# musicbox.net
KiCad netlist of a schematic drawn in EAGLE
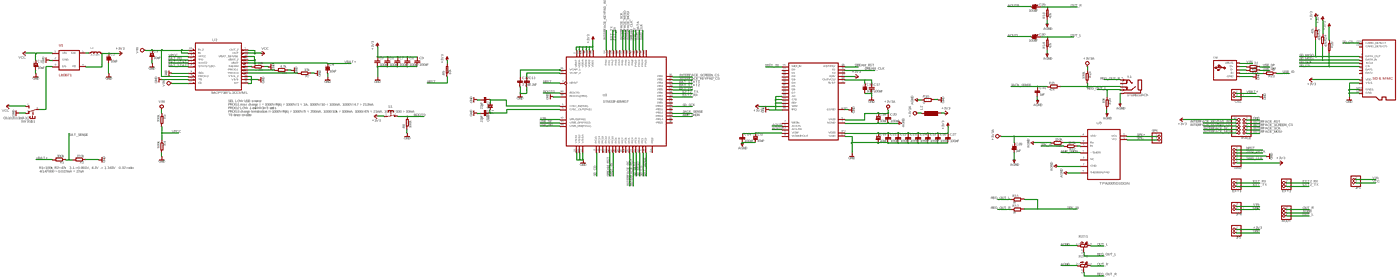
[diagram p0: schematic, sheet 1, overview]
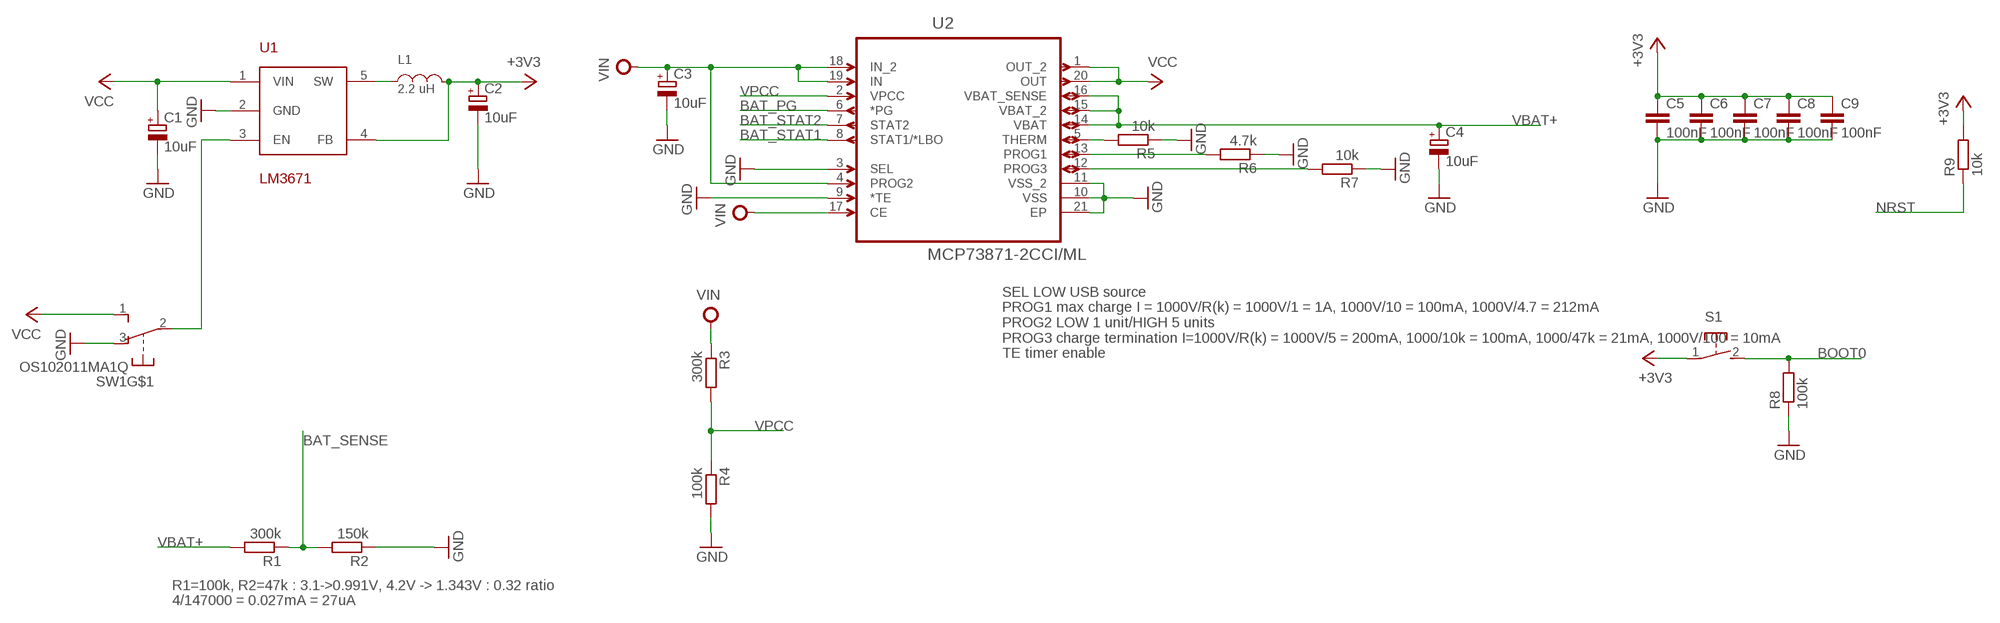
[diagram p1: schematic, sheet 1, part 1 of 4]
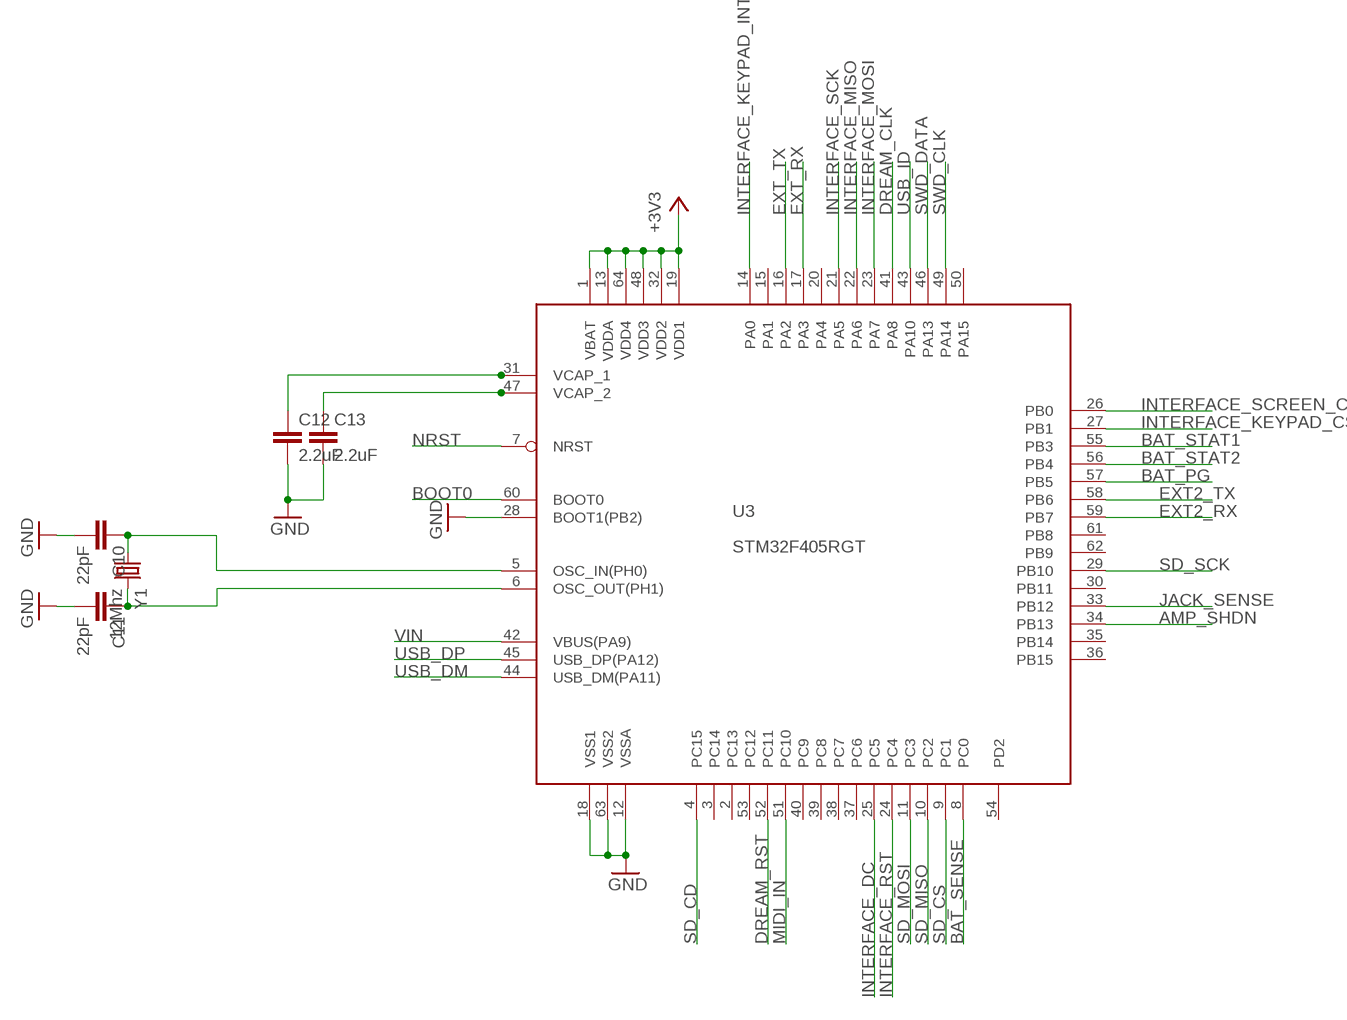
[diagram p2: schematic, sheet 1, part 2 of 4]
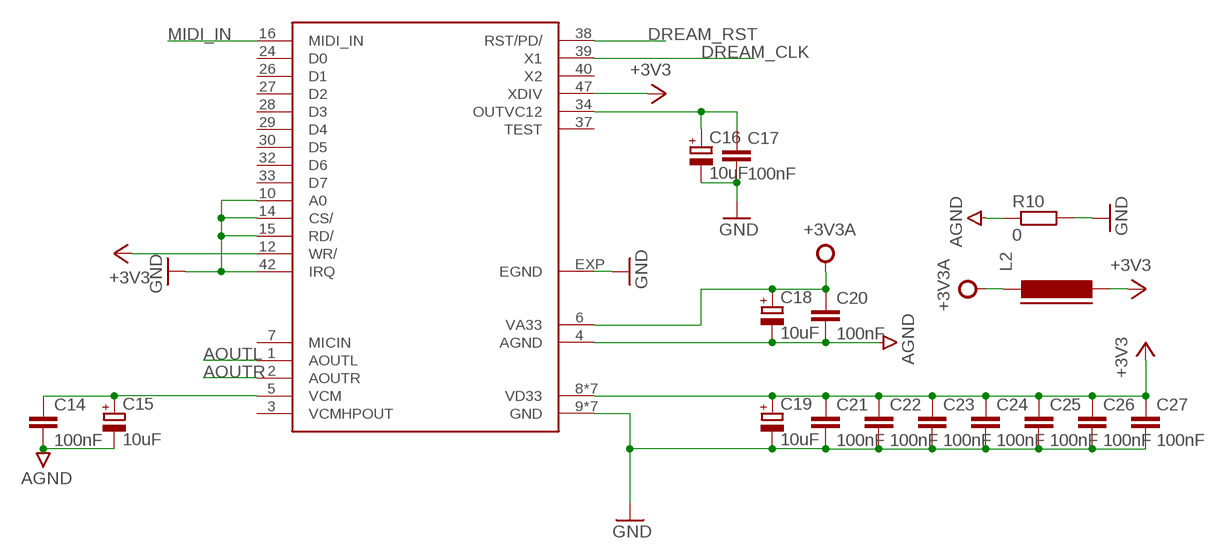
[diagram p3: schematic, sheet 1, part 3 of 4]
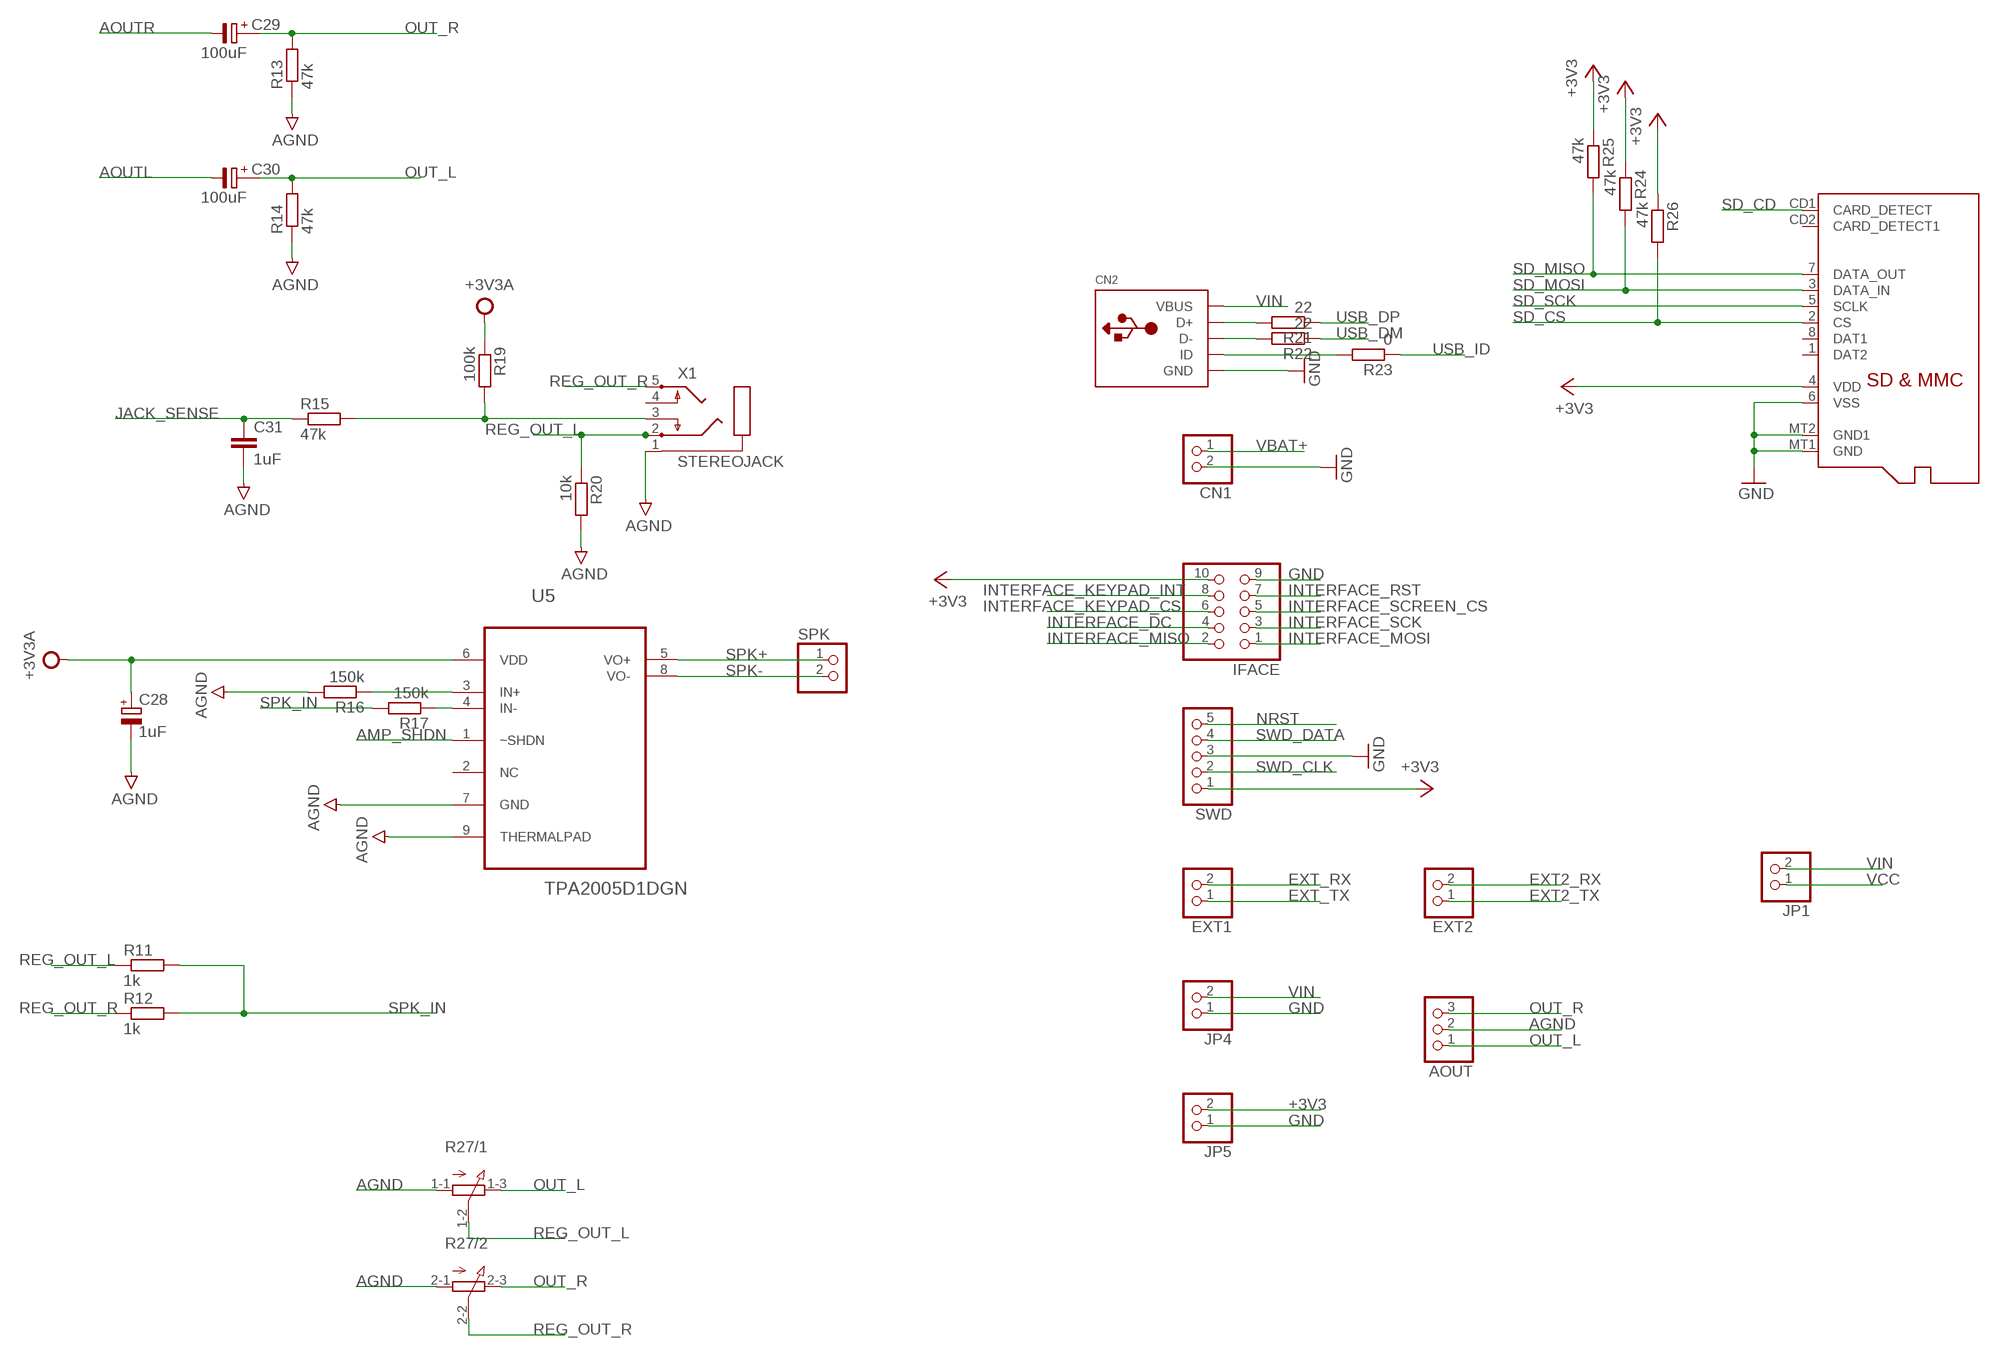
[diagram p4: schematic, sheet 1, part 4 of 4]

(export (version "E")
  (design (tool "Eeschema 10.0.6"))
  (components
    (comp (ref "AOUT")
      (value "HEADER-1X3ROUND")
      (footprint "eagle-import:1X03_ROUND")
      (libsource (lib "eagle-import") (part "HEADER-1X3ROUND"))
    )
    (comp (ref "C1")
      (value "10uF")
      (footprint "eagle-import:A_3216-18R")
      (libsource (lib "eagle-import") (part "CPOL-EUA/3216-18R"))
    )
    (comp (ref "C2")
      (value "10uF")
      (footprint "eagle-import:A_3216-18R")
      (libsource (lib "eagle-import") (part "CPOL-EUA/3216-18R"))
    )
    (comp (ref "C3")
      (value "10uF")
      (footprint "eagle-import:A_3216-18R")
      (libsource (lib "eagle-import") (part "CPOL-EUA/3216-18R"))
    )
    (comp (ref "C4")
      (value "10uF")
      (footprint "eagle-import:A_3216-18R")
      (libsource (lib "eagle-import") (part "CPOL-EUA/3216-18R"))
    )
    (comp (ref "C5")
      (value "100nF")
      (footprint "eagle-import:C0603K")
      (libsource (lib "eagle-import") (part "C-EUC0603K"))
    )
    (comp (ref "C6")
      (value "100nF")
      (footprint "eagle-import:C0603K")
      (libsource (lib "eagle-import") (part "C-EUC0603K"))
    )
    (comp (ref "C7")
      (value "100nF")
      (footprint "eagle-import:C0603K")
      (libsource (lib "eagle-import") (part "C-EUC0603K"))
    )
    (comp (ref "C8")
      (value "100nF")
      (footprint "eagle-import:C0603K")
      (libsource (lib "eagle-import") (part "C-EUC0603K"))
    )
    (comp (ref "C9")
      (value "100nF")
      (footprint "eagle-import:C0603K")
      (libsource (lib "eagle-import") (part "C-EUC0603K"))
    )
    (comp (ref "C10")
      (value "22pF")
      (footprint "eagle-import:C0603K")
      (libsource (lib "eagle-import") (part "C-EUC0603K"))
    )
    (comp (ref "C11")
      (value "22pF")
      (footprint "eagle-import:C0603K")
      (libsource (lib "eagle-import") (part "C-EUC0603K"))
    )
    (comp (ref "C12")
      (value "2.2uF")
      (footprint "eagle-import:C0603K")
      (libsource (lib "eagle-import") (part "C-EUC0603K"))
    )
    (comp (ref "C13")
      (value "2.2uF")
      (footprint "eagle-import:C0603K")
      (libsource (lib "eagle-import") (part "C-EUC0603K"))
    )
    (comp (ref "C14")
      (value "100nF")
      (footprint "eagle-import:C0603K")
      (libsource (lib "eagle-import") (part "C-EUC0603K"))
    )
    (comp (ref "C15")
      (value "10uF")
      (footprint "eagle-import:A_3216-18R")
      (libsource (lib "eagle-import") (part "CPOL-EUA/3216-18R"))
    )
    (comp (ref "C16")
      (value "10uF")
      (footprint "eagle-import:A_3216-18R")
      (libsource (lib "eagle-import") (part "CPOL-EUA/3216-18R"))
    )
    (comp (ref "C17")
      (value "100nF")
      (footprint "eagle-import:C0603K")
      (libsource (lib "eagle-import") (part "C-EUC0603K"))
    )
    (comp (ref "C18")
      (value "10uF")
      (footprint "eagle-import:A_3216-18R")
      (libsource (lib "eagle-import") (part "CPOL-EUA/3216-18R"))
    )
    (comp (ref "C19")
      (value "10uF")
      (footprint "eagle-import:A_3216-18R")
      (libsource (lib "eagle-import") (part "CPOL-EUA/3216-18R"))
    )
    (comp (ref "C20")
      (value "100nF")
      (footprint "eagle-import:C0603K")
      (libsource (lib "eagle-import") (part "C-EUC0603K"))
    )
    (comp (ref "C21")
      (value "100nF")
      (footprint "eagle-import:C0603K")
      (libsource (lib "eagle-import") (part "C-EUC0603K"))
    )
    (comp (ref "C22")
      (value "100nF")
      (footprint "eagle-import:C0603K")
      (libsource (lib "eagle-import") (part "C-EUC0603K"))
    )
    (comp (ref "C23")
      (value "100nF")
      (footprint "eagle-import:C0603K")
      (libsource (lib "eagle-import") (part "C-EUC0603K"))
    )
    (comp (ref "C24")
      (value "100nF")
      (footprint "eagle-import:C0603K")
      (libsource (lib "eagle-import") (part "C-EUC0603K"))
    )
    (comp (ref "C25")
      (value "100nF")
      (footprint "eagle-import:C0603K")
      (libsource (lib "eagle-import") (part "C-EUC0603K"))
    )
    (comp (ref "C26")
      (value "100nF")
      (footprint "eagle-import:C0603K")
      (libsource (lib "eagle-import") (part "C-EUC0603K"))
    )
    (comp (ref "C27")
      (value "100nF")
      (footprint "eagle-import:C0603K")
      (libsource (lib "eagle-import") (part "C-EUC0603K"))
    )
    (comp (ref "C28")
      (value "1uF")
      (footprint "eagle-import:A_3216-18R")
      (libsource (lib "eagle-import") (part "CPOL-EUA/3216-18R"))
    )
    (comp (ref "C29")
      (value "100uF")
      (footprint "eagle-import:SV-B")
      (libsource (lib "eagle-import") (part "C-PR-SMD-SV-B"))
    )
    (comp (ref "C30")
      (value "100uF")
      (footprint "eagle-import:SV-B")
      (libsource (lib "eagle-import") (part "C-PR-SMD-SV-B"))
    )
    (comp (ref "C31")
      (value "1uF")
      (footprint "eagle-import:C0603K")
      (libsource (lib "eagle-import") (part "C-EUC0603K"))
    )
    (comp (ref "CN1")
      (value "JST_2PIN-THM")
      (footprint "eagle-import:JST-PH-2-THM")
      (libsource (lib "eagle-import") (part "JST_2PIN-THM"))
    )
    (comp (ref "CN2")
      (value "USBMOLEX")
      (footprint "eagle-import:USB-MINIB-THM-MOLEX")
      (libsource (lib "eagle-import") (part "USBMOLEX"))
    )
    (comp (ref "EXT1")
      (value "HEADER-1X2ROUND")
      (footprint "eagle-import:1X02_ROUND")
      (libsource (lib "eagle-import") (part "HEADER-1X2ROUND"))
    )
    (comp (ref "EXT2")
      (value "HEADER-1X2ROUND")
      (footprint "eagle-import:1X02_ROUND")
      (libsource (lib "eagle-import") (part "HEADER-1X2ROUND"))
    )
    (comp (ref "IFACE")
      (value "HEADER-2X5")
      (footprint "eagle-import:2X05")
      (libsource (lib "eagle-import") (part "HEADER-2X5"))
    )
    (comp (ref "JP1")
      (value "HEADER-1X2ROUND")
      (footprint "eagle-import:1X02_ROUND")
      (libsource (lib "eagle-import") (part "HEADER-1X2ROUND"))
    )
    (comp (ref "JP4")
      (value "HEADER-1X2ROUND")
      (footprint "eagle-import:1X02_ROUND")
      (libsource (lib "eagle-import") (part "HEADER-1X2ROUND"))
    )
    (comp (ref "JP5")
      (value "HEADER-1X2ROUND")
      (footprint "eagle-import:1X02_ROUND")
      (libsource (lib "eagle-import") (part "HEADER-1X2ROUND"))
    )
    (comp (ref "L1")
      (value "2.2 uH")
      (footprint "eagle-import:4X4MM")
      (libsource (lib "eagle-import") (part "L4X4MM"))
    )
    (comp (ref "L2")
      (value "FERRITE-0603")
      (footprint "eagle-import:FB603")
      (libsource (lib "eagle-import") (part "FERRITE-0603"))
    )
    (comp (ref "R1")
      (value "300k")
      (footprint "eagle-import:R0603")
      (libsource (lib "eagle-import") (part "R-EU_R0603"))
    )
    (comp (ref "R2")
      (value "150k")
      (footprint "eagle-import:R0603")
      (libsource (lib "eagle-import") (part "R-EU_R0603"))
    )
    (comp (ref "R3")
      (value "300k")
      (footprint "eagle-import:R0603")
      (libsource (lib "eagle-import") (part "R-EU_R0603"))
    )
    (comp (ref "R4")
      (value "100k")
      (footprint "eagle-import:R0603")
      (libsource (lib "eagle-import") (part "R-EU_R0603"))
    )
    (comp (ref "R5")
      (value "10k")
      (footprint "eagle-import:R0603")
      (libsource (lib "eagle-import") (part "R-EU_R0603"))
    )
    (comp (ref "R6")
      (value "4.7k")
      (footprint "eagle-import:R0603")
      (libsource (lib "eagle-import") (part "R-EU_R0603"))
    )
    (comp (ref "R7")
      (value "10k")
      (footprint "eagle-import:R0603")
      (libsource (lib "eagle-import") (part "R-EU_R0603"))
    )
    (comp (ref "R8")
      (value "100k")
      (footprint "eagle-import:R0603")
      (libsource (lib "eagle-import") (part "R-EU_R0603"))
    )
    (comp (ref "R9")
      (value "10k")
      (footprint "eagle-import:R0603")
      (libsource (lib "eagle-import") (part "R-EU_R0603"))
    )
    (comp (ref "R10")
      (value "0")
      (footprint "eagle-import:R0603")
      (libsource (lib "eagle-import") (part "R-EU_R0603"))
    )
    (comp (ref "R11")
      (value "1k")
      (footprint "eagle-import:R0603")
      (libsource (lib "eagle-import") (part "R-EU_R0603"))
    )
    (comp (ref "R12")
      (value "1k")
      (footprint "eagle-import:R0603")
      (libsource (lib "eagle-import") (part "R-EU_R0603"))
    )
    (comp (ref "R13")
      (value "47k")
      (footprint "eagle-import:R0603")
      (libsource (lib "eagle-import") (part "R-EU_R0603"))
    )
    (comp (ref "R14")
      (value "47k")
      (footprint "eagle-import:R0603")
      (libsource (lib "eagle-import") (part "R-EU_R0603"))
    )
    (comp (ref "R15")
      (value "47k")
      (footprint "eagle-import:R0603")
      (libsource (lib "eagle-import") (part "R-EU_R0603"))
    )
    (comp (ref "R16")
      (value "150k")
      (footprint "eagle-import:R0603")
      (libsource (lib "eagle-import") (part "R-EU_R0603"))
    )
    (comp (ref "R17")
      (value "150k")
      (footprint "eagle-import:R0603")
      (libsource (lib "eagle-import") (part "R-EU_R0603"))
    )
    (comp (ref "R19")
      (value "100k")
      (footprint "eagle-import:R0603")
      (libsource (lib "eagle-import") (part "R-EU_R0603"))
    )
    (comp (ref "R20")
      (value "10k")
      (footprint "eagle-import:R0603")
      (libsource (lib "eagle-import") (part "R-EU_R0603"))
    )
    (comp (ref "R21")
      (value "22")
      (footprint "eagle-import:R0603")
      (libsource (lib "eagle-import") (part "R-EU_R0603"))
    )
    (comp (ref "R22")
      (value "22")
      (footprint "eagle-import:R0603")
      (libsource (lib "eagle-import") (part "R-EU_R0603"))
    )
    (comp (ref "R23")
      (value "0")
      (footprint "eagle-import:R0603")
      (libsource (lib "eagle-import") (part "R-EU_R0603"))
    )
    (comp (ref "R24")
      (value "47k")
      (footprint "eagle-import:R0603")
      (libsource (lib "eagle-import") (part "R-EU_R0603"))
    )
    (comp (ref "R25")
      (value "47k")
      (footprint "eagle-import:R0603")
      (libsource (lib "eagle-import") (part "R-EU_R0603"))
    )
    (comp (ref "R26")
      (value "47k")
      (footprint "eagle-import:R0603")
      (libsource (lib "eagle-import") (part "R-EU_R0603"))
    )
    (comp (ref "R27")
      (value "3RP/1610G")
      (footprint "eagle-import:3RP_1610G")
      (libsource (lib "eagle-import") (part "3RP/1610G"))
    )
    (comp (ref "S1")
      (value "31-XX")
      (footprint "eagle-import:B3F-31XX")
      (fields (field (name "MPN") "B3F-3100"))
      (libsource (lib "eagle-import") (part "31-XX"))
    )
    (comp (ref "SPK")
      (value "HEADER-1X2ROUND")
      (footprint "eagle-import:1X02_ROUND")
      (libsource (lib "eagle-import") (part "HEADER-1X2ROUND"))
    )
    (comp (ref "SW1")
      (value "OS102011MA1Q")
      (footprint "eagle-import:OS102011MA1Q")
      (libsource (lib "eagle-import") (part "OS102011MA1Q"))
    )
    (comp (ref "SWD")
      (value "HEADER-1X5ROUND")
      (footprint "eagle-import:1X05_ROUND")
      (libsource (lib "eagle-import") (part "HEADER-1X5ROUND"))
    )
    (comp (ref "U1")
      (value "LM3671")
      (footprint "eagle-import:SOT23-5")
      (libsource (lib "eagle-import") (part "LM3671"))
    )
    (comp (ref "U2")
      (value "MCP73871-2CCI/ML")
      (footprint "eagle-import:QFN50P400X400X100-21N")
      (libsource (lib "eagle-import") (part "MCP73871-2CCI/ML"))
    )
    (comp (ref "U3")
      (value "STM32F405RGT")
      (footprint "eagle-import:LQFP64")
      (libsource (lib "eagle-import") (part "STM32F405RGT"))
    )
    (comp (ref "U4")
      (value "SAM2695")
      (footprint "eagle-import:QFN48")
      (libsource (lib "eagle-import") (part "SAM2695"))
    )
    (comp (ref "U5")
      (value "TPA2005D1DGN")
      (footprint "eagle-import:SOP65P488X107-9N")
      (libsource (lib "eagle-import") (part "TPA2005D1DGN"))
    )
    (comp (ref "U6")
      (value "MICROSD")
      (footprint "eagle-import:MICROSD")
      (libsource (lib "eagle-import") (part "MICROSD"))
    )
    (comp (ref "X1")
      (value "STEREOJACK")
      (footprint "eagle-import:STX3100")
      (libsource (lib "eagle-import") (part "STEREOJACK"))
    )
    (comp (ref "Y1")
      (value "12Mhz")
      (footprint "eagle-import:CRYSTAL-TXC-7A")
      (libsource (lib "eagle-import") (part "CRYSTALTXC-7A"))
    )
  )
  (nets
    (net (code "1") (name "+3V3") (class "Default")
      (node (ref "C19") (pin "+") (pinfunction "+_+") (pintype "passive"))
      (node (ref "C2") (pin "+") (pinfunction "+_+") (pintype "passive"))
      (node (ref "C21") (pin "1") (pinfunction "1_1") (pintype "passive"))
      (node (ref "C22") (pin "1") (pinfunction "1_1") (pintype "passive"))
      (node (ref "C23") (pin "1") (pinfunction "1_1") (pintype "passive"))
      (node (ref "C24") (pin "1") (pinfunction "1_1") (pintype "passive"))
      (node (ref "C25") (pin "1") (pinfunction "1_1") (pintype "passive"))
      (node (ref "C26") (pin "1") (pinfunction "1_1") (pintype "passive"))
      (node (ref "C27") (pin "1") (pinfunction "1_1") (pintype "passive"))
      (node (ref "C5") (pin "1") (pinfunction "1_1") (pintype "passive"))
      (node (ref "C6") (pin "1") (pinfunction "1_1") (pintype "passive"))
      (node (ref "C7") (pin "1") (pinfunction "1_1") (pintype "passive"))
      (node (ref "C8") (pin "1") (pinfunction "1_1") (pintype "passive"))
      (node (ref "C9") (pin "1") (pinfunction "1_1") (pintype "passive"))
      (node (ref "IFACE") (pin "10") (pinfunction "10_10") (pintype "passive"))
      (node (ref "JP5") (pin "2") (pinfunction "2_2") (pintype "passive"))
      (node (ref "L1") (pin "2") (pinfunction "2_2") (pintype "passive"))
      (node (ref "L2") (pin "2") (pinfunction "2_2") (pintype "passive"))
      (node (ref "R24") (pin "1") (pinfunction "1_1") (pintype "passive"))
      (node (ref "R25") (pin "1") (pinfunction "1_1") (pintype "passive"))
      (node (ref "R26") (pin "1") (pinfunction "1_1") (pintype "passive"))
      (node (ref "R9") (pin "2") (pinfunction "2_2") (pintype "passive"))
      (node (ref "S1") (pin "1") (pinfunction "P_1") (pintype "passive"))
      (node (ref "SWD") (pin "1") (pinfunction "1_1") (pintype "passive"))
      (node (ref "U1") (pin "4") (pinfunction "FB_4") (pintype "bidirectional"))
      (node (ref "U3") (pin "1") (pinfunction "VBAT_1") (pintype "power_in"))
      (node (ref "U3") (pin "13") (pinfunction "VDDA_13") (pintype "power_in"))
      (node (ref "U3") (pin "19") (pinfunction "VDD1_19") (pintype "power_in"))
      (node (ref "U3") (pin "32") (pinfunction "VDD2_32") (pintype "power_in"))
      (node (ref "U3") (pin "48") (pinfunction "VDD3_48") (pintype "power_in"))
      (node (ref "U3") (pin "64") (pinfunction "VDD4_64") (pintype "power_in"))
      (node (ref "U4") (pin "11") (pinfunction "VD33_11") (pintype "power_in"))
      (node (ref "U4") (pin "12") (pinfunction "WR/_12") (pintype "input"))
      (node (ref "U4") (pin "20") (pinfunction "VD33_20") (pintype "power_in"))
      (node (ref "U4") (pin "31") (pinfunction "VD33_31") (pintype "power_in"))
      (node (ref "U4") (pin "35") (pinfunction "VD33_35") (pintype "power_in"))
      (node (ref "U4") (pin "41") (pinfunction "VD33_41") (pintype "power_in"))
      (node (ref "U4") (pin "46") (pinfunction "VD33_46") (pintype "power_in"))
      (node (ref "U4") (pin "47") (pinfunction "XDIV_47") (pintype "input"))
      (node (ref "U4") (pin "8") (pinfunction "VD33_8") (pintype "power_in"))
      (node (ref "U6") (pin "4") (pinfunction "VDD_4") (pintype "power_in"))
    )
    (net (code "2") (name "+3V3A") (class "Default")
      (node (ref "C18") (pin "+") (pinfunction "+_+") (pintype "passive"))
      (node (ref "C20") (pin "1") (pinfunction "1_1") (pintype "passive"))
      (node (ref "C28") (pin "+") (pinfunction "+_+") (pintype "passive"))
      (node (ref "L2") (pin "1") (pinfunction "1_1") (pintype "passive"))
      (node (ref "R19") (pin "1") (pinfunction "1_1") (pintype "passive"))
      (node (ref "U4") (pin "6") (pinfunction "VA33_6") (pintype "power_in"))
      (node (ref "U5") (pin "6") (pinfunction "VDD_6") (pintype "power_in"))
    )
    (net (code "3") (name "/AMP_SHDN") (class "Default")
      (node (ref "U3") (pin "34") (pinfunction "PB13_34") (pintype "bidirectional"))
      (node (ref "U5") (pin "1") (pinfunction "~{SHDN}_1") (pintype "passive"))
    )
    (net (code "4") (name "/AOUTL") (class "Default")
      (node (ref "C30") (pin "-") (pinfunction "-_-") (pintype "passive"))
      (node (ref "U4") (pin "1") (pinfunction "AOUTL_1") (pintype "output"))
    )
    (net (code "5") (name "/AOUTR") (class "Default")
      (node (ref "C29") (pin "-") (pinfunction "-_-") (pintype "passive"))
      (node (ref "U4") (pin "2") (pinfunction "AOUTR_2") (pintype "output"))
    )
    (net (code "6") (name "/BAT_PG") (class "Default")
      (node (ref "U2") (pin "6") (pinfunction "*PG_6") (pintype "output"))
      (node (ref "U3") (pin "57") (pinfunction "PB5_57") (pintype "bidirectional"))
    )
    (net (code "7") (name "/BAT_SENSE") (class "Default")
      (node (ref "R1") (pin "1") (pinfunction "1_1") (pintype "passive"))
      (node (ref "R2") (pin "2") (pinfunction "2_2") (pintype "passive"))
      (node (ref "U3") (pin "8") (pinfunction "PC0_8") (pintype "bidirectional"))
    )
    (net (code "8") (name "/BAT_STAT1") (class "Default")
      (node (ref "U2") (pin "8") (pinfunction "STAT1/*LBO_8") (pintype "output"))
      (node (ref "U3") (pin "55") (pinfunction "PB3_55") (pintype "bidirectional"))
    )
    (net (code "9") (name "/BAT_STAT2") (class "Default")
      (node (ref "U2") (pin "7") (pinfunction "STAT2_7") (pintype "output"))
      (node (ref "U3") (pin "56") (pinfunction "PB4_56") (pintype "bidirectional"))
    )
    (net (code "10") (name "/BOOT0") (class "Default")
      (node (ref "R8") (pin "2") (pinfunction "2_2") (pintype "passive"))
      (node (ref "S1") (pin "2") (pinfunction "S_2") (pintype "passive"))
      (node (ref "U3") (pin "60") (pinfunction "BOOT0_60") (pintype "input"))
    )
    (net (code "11") (name "/DREAM_CLK") (class "Default")
      (node (ref "U3") (pin "41") (pinfunction "PA8_41") (pintype "bidirectional"))
      (node (ref "U4") (pin "39") (pinfunction "X1_39") (pintype "bidirectional"))
    )
    (net (code "12") (name "/DREAM_RST") (class "Default")
      (node (ref "U3") (pin "52") (pinfunction "PC11_52") (pintype "bidirectional"))
      (node (ref "U4") (pin "38") (pinfunction "RST/PD/_38") (pintype "input"))
    )
    (net (code "13") (name "/EXT2_RX") (class "Default")
      (node (ref "EXT2") (pin "2") (pinfunction "2_2") (pintype "passive"))
      (node (ref "U3") (pin "59") (pinfunction "PB7_59") (pintype "bidirectional"))
    )
    (net (code "14") (name "/EXT2_TX") (class "Default")
      (node (ref "EXT2") (pin "1") (pinfunction "1_1") (pintype "passive"))
      (node (ref "U3") (pin "58") (pinfunction "PB6_58") (pintype "bidirectional"))
    )
    (net (code "15") (name "/EXT_RX") (class "Default")
      (node (ref "EXT1") (pin "2") (pinfunction "2_2") (pintype "passive"))
      (node (ref "U3") (pin "17") (pinfunction "PA3_17") (pintype "bidirectional"))
    )
    (net (code "16") (name "/EXT_TX") (class "Default")
      (node (ref "EXT1") (pin "1") (pinfunction "1_1") (pintype "passive"))
      (node (ref "U3") (pin "16") (pinfunction "PA2_16") (pintype "bidirectional"))
    )
    (net (code "17") (name "/INTERFACE_DC") (class "Default")
      (node (ref "IFACE") (pin "4") (pinfunction "4_4") (pintype "passive"))
      (node (ref "U3") (pin "25") (pinfunction "PC5_25") (pintype "bidirectional"))
    )
    (net (code "18") (name "/INTERFACE_KEYPAD_CS") (class "Default")
      (node (ref "IFACE") (pin "6") (pinfunction "6_6") (pintype "passive"))
      (node (ref "U3") (pin "27") (pinfunction "PB1_27") (pintype "bidirectional"))
    )
    (net (code "19") (name "/INTERFACE_KEYPAD_INT") (class "Default")
      (node (ref "IFACE") (pin "8") (pinfunction "8_8") (pintype "passive"))
      (node (ref "U3") (pin "14") (pinfunction "PA0_14") (pintype "bidirectional"))
    )
    (net (code "20") (name "/INTERFACE_MISO") (class "Default")
      (node (ref "IFACE") (pin "2") (pinfunction "2_2") (pintype "passive"))
      (node (ref "U3") (pin "22") (pinfunction "PA6_22") (pintype "bidirectional"))
    )
    (net (code "21") (name "/INTERFACE_MOSI") (class "Default")
      (node (ref "IFACE") (pin "1") (pinfunction "1_1") (pintype "passive"))
      (node (ref "U3") (pin "23") (pinfunction "PA7_23") (pintype "bidirectional"))
    )
    (net (code "22") (name "/INTERFACE_RST") (class "Default")
      (node (ref "IFACE") (pin "7") (pinfunction "7_7") (pintype "passive"))
      (node (ref "U3") (pin "24") (pinfunction "PC4_24") (pintype "bidirectional"))
    )
    (net (code "23") (name "/INTERFACE_SCK") (class "Default")
      (node (ref "IFACE") (pin "3") (pinfunction "3_3") (pintype "passive"))
      (node (ref "U3") (pin "21") (pinfunction "PA5_21") (pintype "bidirectional"))
    )
    (net (code "24") (name "/INTERFACE_SCREEN_CS") (class "Default")
      (node (ref "IFACE") (pin "5") (pinfunction "5_5") (pintype "passive"))
      (node (ref "U3") (pin "26") (pinfunction "PB0_26") (pintype "bidirectional"))
    )
    (net (code "25") (name "/JACK_SENSE") (class "Default")
      (node (ref "C31") (pin "1") (pinfunction "1_1") (pintype "passive"))
      (node (ref "R15") (pin "1") (pinfunction "1_1") (pintype "passive"))
      (node (ref "U3") (pin "33") (pinfunction "PB12_33") (pintype "bidirectional"))
    )
    (net (code "26") (name "/MIDI_IN") (class "Default")
      (node (ref "U3") (pin "51") (pinfunction "PC10_51") (pintype "bidirectional"))
      (node (ref "U4") (pin "16") (pinfunction "MIDI_IN_16") (pintype "input"))
    )
    (net (code "27") (name "/NRST") (class "Default")
      (node (ref "R9") (pin "1") (pinfunction "1_1") (pintype "passive"))
      (node (ref "SWD") (pin "5") (pinfunction "5_5") (pintype "passive"))
      (node (ref "U3") (pin "7") (pinfunction "NRST_7") (pintype "input"))
    )
    (net (code "28") (name "/OUT_L") (class "Default")
      (node (ref "AOUT") (pin "1") (pinfunction "1_1") (pintype "passive"))
      (node (ref "C30") (pin "+") (pinfunction "+_+") (pintype "passive"))
      (node (ref "R14") (pin "2") (pinfunction "2_2") (pintype "passive"))
      (node (ref "R27") (pin "1-3") (pinfunction "E_1-3") (pintype "passive"))
    )
    (net (code "29") (name "/OUT_R") (class "Default")
      (node (ref "AOUT") (pin "3") (pinfunction "3_3") (pintype "passive"))
      (node (ref "C29") (pin "+") (pinfunction "+_+") (pintype "passive"))
      (node (ref "R13") (pin "2") (pinfunction "2_2") (pintype "passive"))
      (node (ref "R27") (pin "2-3") (pinfunction "E_2-3") (pintype "passive"))
    )
    (net (code "30") (name "/REG_OUT_L") (class "Default")
      (node (ref "R11") (pin "1") (pinfunction "1_1") (pintype "passive"))
      (node (ref "R20") (pin "1") (pinfunction "1_1") (pintype "passive"))
      (node (ref "R27") (pin "1-2") (pinfunction "S_1-2") (pintype "passive"))
      (node (ref "X1") (pin "2") (pinfunction "2_2") (pintype "passive"))
    )
    (net (code "31") (name "/REG_OUT_R") (class "Default")
      (node (ref "R12") (pin "1") (pinfunction "1_1") (pintype "passive"))
      (node (ref "R27") (pin "2-2") (pinfunction "S_2-2") (pintype "passive"))
      (node (ref "X1") (pin "5") (pinfunction "5_5") (pintype "passive"))
    )
    (net (code "32") (name "/SD_CD") (class "Default")
      (node (ref "U3") (pin "4") (pinfunction "PC15_4") (pintype "bidirectional"))
      (node (ref "U6") (pin "CD1") (pinfunction "CARD_DETECT_CD1") (pintype "passive"))
    )
    (net (code "33") (name "/SD_CS") (class "Default")
      (node (ref "R26") (pin "2") (pinfunction "2_2") (pintype "passive"))
      (node (ref "U3") (pin "9") (pinfunction "PC1_9") (pintype "bidirectional"))
      (node (ref "U6") (pin "2") (pinfunction "CS_2") (pintype "input"))
    )
    (net (code "34") (name "/SD_MISO") (class "Default")
      (node (ref "R25") (pin "2") (pinfunction "2_2") (pintype "passive"))
      (node (ref "U3") (pin "10") (pinfunction "PC2_10") (pintype "bidirectional"))
      (node (ref "U6") (pin "7") (pinfunction "DATA_OUT_7") (pintype "output"))
    )
    (net (code "35") (name "/SD_MOSI") (class "Default")
      (node (ref "R24") (pin "2") (pinfunction "2_2") (pintype "passive"))
      (node (ref "U3") (pin "11") (pinfunction "PC3_11") (pintype "bidirectional"))
      (node (ref "U6") (pin "3") (pinfunction "DATA_IN_3") (pintype "input"))
    )
    (net (code "36") (name "/SD_SCK") (class "Default")
      (node (ref "U3") (pin "29") (pinfunction "PB10_29") (pintype "bidirectional"))
      (node (ref "U6") (pin "5") (pinfunction "SCLK_5") (pintype "input"))
    )
    (net (code "37") (name "/SPK+") (class "Default")
      (node (ref "SPK") (pin "1") (pinfunction "1_1") (pintype "passive"))
      (node (ref "U5") (pin "5") (pinfunction "VO+_5") (pintype "output"))
    )
    (net (code "38") (name "/SPK-") (class "Default")
      (node (ref "SPK") (pin "2") (pinfunction "2_2") (pintype "passive"))
      (node (ref "U5") (pin "8") (pinfunction "VO-_8") (pintype "output"))
    )
    (net (code "39") (name "/SPK_IN") (class "Default")
      (node (ref "R11") (pin "2") (pinfunction "2_2") (pintype "passive"))
      (node (ref "R12") (pin "2") (pinfunction "2_2") (pintype "passive"))
      (node (ref "R17") (pin "2") (pinfunction "2_2") (pintype "passive"))
    )
    (net (code "40") (name "/SWD_CLK") (class "Default")
      (node (ref "SWD") (pin "2") (pinfunction "2_2") (pintype "passive"))
      (node (ref "U3") (pin "49") (pinfunction "PA14_49") (pintype "bidirectional"))
    )
    (net (code "41") (name "/SWD_DATA") (class "Default")
      (node (ref "SWD") (pin "4") (pinfunction "4_4") (pintype "passive"))
      (node (ref "U3") (pin "46") (pinfunction "PA13_46") (pintype "bidirectional"))
    )
    (net (code "42") (name "/USB_DM") (class "Default")
      (node (ref "R22") (pin "1") (pinfunction "1_1") (pintype "passive"))
      (node (ref "U3") (pin "44") (pinfunction "USB_DM(PA11)_44") (pintype "bidirectional"))
    )
    (net (code "43") (name "/USB_DP") (class "Default")
      (node (ref "R21") (pin "1") (pinfunction "1_1") (pintype "passive"))
      (node (ref "U3") (pin "45") (pinfunction "USB_DP(PA12)_45") (pintype "bidirectional"))
    )
    (net (code "44") (name "/USB_ID") (class "Default")
      (node (ref "R23") (pin "1") (pinfunction "1_1") (pintype "passive"))
      (node (ref "U3") (pin "43") (pinfunction "PA10_43") (pintype "bidirectional"))
    )
    (net (code "45") (name "/VBAT+") (class "Default")
      (node (ref "C4") (pin "+") (pinfunction "+_+") (pintype "passive"))
      (node (ref "CN1") (pin "1") (pinfunction "2_1") (pintype "passive"))
      (node (ref "R1") (pin "2") (pinfunction "2_2") (pintype "passive"))
      (node (ref "U2") (pin "14") (pinfunction "VBAT_14") (pintype "bidirectional"))
      (node (ref "U2") (pin "15") (pinfunction "VBAT_2_15") (pintype "bidirectional"))
      (node (ref "U2") (pin "16") (pinfunction "VBAT_SENSE_16") (pintype "bidirectional"))
    )
    (net (code "46") (name "/VPCC") (class "Default")
      (node (ref "R3") (pin "2") (pinfunction "2_2") (pintype "passive"))
      (node (ref "R4") (pin "1") (pinfunction "1_1") (pintype "passive"))
      (node (ref "U2") (pin "2") (pinfunction "VPCC_2") (pintype "input"))
    )
    (net (code "47") (name "AGND") (class "Default")
      (node (ref "AOUT") (pin "2") (pinfunction "2_2") (pintype "passive"))
      (node (ref "C14") (pin "2") (pinfunction "2_2") (pintype "passive"))
      (node (ref "C15") (pin "-") (pinfunction "-_-") (pintype "passive"))
      (node (ref "C18") (pin "-") (pinfunction "-_-") (pintype "passive"))
      (node (ref "C20") (pin "2") (pinfunction "2_2") (pintype "passive"))
      (node (ref "C28") (pin "-") (pinfunction "-_-") (pintype "passive"))
      (node (ref "C31") (pin "2") (pinfunction "2_2") (pintype "passive"))
      (node (ref "R10") (pin "1") (pinfunction "1_1") (pintype "passive"))
      (node (ref "R13") (pin "1") (pinfunction "1_1") (pintype "passive"))
      (node (ref "R14") (pin "1") (pinfunction "1_1") (pintype "passive"))
      (node (ref "R16") (pin "2") (pinfunction "2_2") (pintype "passive"))
      (node (ref "R20") (pin "2") (pinfunction "2_2") (pintype "passive"))
      (node (ref "R27") (pin "1-1") (pinfunction "A_1-1") (pintype "passive"))
      (node (ref "R27") (pin "2-1") (pinfunction "A_2-1") (pintype "passive"))
      (node (ref "U4") (pin "4") (pinfunction "AGND_4") (pintype "power_in"))
      (node (ref "U5") (pin "7") (pinfunction "GND_7") (pintype "passive"))
      (node (ref "U5") (pin "9") (pinfunction "THERMALPAD_9") (pintype "passive"))
      (node (ref "X1") (pin "1") (pinfunction "1_1") (pintype "passive"))
    )
    (net (code "48") (name "GND") (class "Default")
      (node (ref "C1") (pin "-") (pinfunction "-_-") (pintype "passive"))
      (node (ref "C10") (pin "2") (pinfunction "2_2") (pintype "passive"))
      (node (ref "C11") (pin "2") (pinfunction "2_2") (pintype "passive"))
      (node (ref "C12") (pin "2") (pinfunction "2_2") (pintype "passive"))
      (node (ref "C13") (pin "2") (pinfunction "2_2") (pintype "passive"))
      (node (ref "C16") (pin "-") (pinfunction "-_-") (pintype "passive"))
      (node (ref "C17") (pin "2") (pinfunction "2_2") (pintype "passive"))
      (node (ref "C19") (pin "-") (pinfunction "-_-") (pintype "passive"))
      (node (ref "C2") (pin "-") (pinfunction "-_-") (pintype "passive"))
      (node (ref "C21") (pin "2") (pinfunction "2_2") (pintype "passive"))
      (node (ref "C22") (pin "2") (pinfunction "2_2") (pintype "passive"))
      (node (ref "C23") (pin "2") (pinfunction "2_2") (pintype "passive"))
      (node (ref "C24") (pin "2") (pinfunction "2_2") (pintype "passive"))
      (node (ref "C25") (pin "2") (pinfunction "2_2") (pintype "passive"))
      (node (ref "C26") (pin "2") (pinfunction "2_2") (pintype "passive"))
      (node (ref "C27") (pin "2") (pinfunction "2_2") (pintype "passive"))
      (node (ref "C3") (pin "-") (pinfunction "-_-") (pintype "passive"))
      (node (ref "C4") (pin "-") (pinfunction "-_-") (pintype "passive"))
      (node (ref "C5") (pin "2") (pinfunction "2_2") (pintype "passive"))
      (node (ref "C6") (pin "2") (pinfunction "2_2") (pintype "passive"))
      (node (ref "C7") (pin "2") (pinfunction "2_2") (pintype "passive"))
      (node (ref "C8") (pin "2") (pinfunction "2_2") (pintype "passive"))
      (node (ref "C9") (pin "2") (pinfunction "2_2") (pintype "passive"))
      (node (ref "CN1") (pin "2") (pinfunction "1_2") (pintype "passive"))
      (node (ref "CN2") (pin "GND") (pinfunction "GND_GND") (pintype "power_in"))
      (node (ref "IFACE") (pin "9") (pinfunction "9_9") (pintype "passive"))
      (node (ref "JP4") (pin "1") (pinfunction "1_1") (pintype "passive"))
      (node (ref "JP5") (pin "1") (pinfunction "1_1") (pintype "passive"))
      (node (ref "R10") (pin "2") (pinfunction "2_2") (pintype "passive"))
      (node (ref "R2") (pin "1") (pinfunction "1_1") (pintype "passive"))
      (node (ref "R4") (pin "2") (pinfunction "2_2") (pintype "passive"))
      (node (ref "R5") (pin "1") (pinfunction "1_1") (pintype "passive"))
      (node (ref "R6") (pin "1") (pinfunction "1_1") (pintype "passive"))
      (node (ref "R7") (pin "1") (pinfunction "1_1") (pintype "passive"))
      (node (ref "R8") (pin "1") (pinfunction "1_1") (pintype "passive"))
      (node (ref "SW1") (pin "3") (pinfunction "O_3") (pintype "passive"))
      (node (ref "SWD") (pin "3") (pinfunction "3_3") (pintype "passive"))
      (node (ref "U1") (pin "2") (pinfunction "GND_2") (pintype "bidirectional"))
      (node (ref "U2") (pin "10") (pinfunction "VSS_10") (pintype "power_in"))
      (node (ref "U2") (pin "11") (pinfunction "VSS_2_11") (pintype "power_in"))
      (node (ref "U2") (pin "21") (pinfunction "EP_21") (pintype "passive"))
      (node (ref "U2") (pin "3") (pinfunction "SEL_3") (pintype "input"))
      (node (ref "U2") (pin "9") (pinfunction "*TE_9") (pintype "input"))
      (node (ref "U3") (pin "12") (pinfunction "VSSA_12") (pintype "power_in"))
      (node (ref "U3") (pin "18") (pinfunction "VSS1_18") (pintype "power_in"))
      (node (ref "U3") (pin "28") (pinfunction "BOOT1(PB2)_28") (pintype "input"))
      (node (ref "U3") (pin "63") (pinfunction "VSS2_63") (pintype "power_in"))
      (node (ref "U4") (pin "10") (pinfunction "A0_10") (pintype "input"))
      (node (ref "U4") (pin "13") (pinfunction "GND_13") (pintype "power_in"))
      (node (ref "U4") (pin "14") (pinfunction "CS/_14") (pintype "input"))
      (node (ref "U4") (pin "15") (pinfunction "RD/_15") (pintype "input"))
      (node (ref "U4") (pin "18") (pinfunction "GND_18") (pintype "power_in"))
      (node (ref "U4") (pin "25") (pinfunction "GND_25") (pintype "power_in"))
      (node (ref "U4") (pin "36") (pinfunction "GND_36") (pintype "power_in"))
      (node (ref "U4") (pin "42") (pinfunction "IRQ_42") (pintype "output"))
      (node (ref "U4") (pin "45") (pinfunction "GND_45") (pintype "power_in"))
      (node (ref "U4") (pin "48") (pinfunction "GND_48") (pintype "power_in"))
      (node (ref "U4") (pin "9") (pinfunction "GND_9") (pintype "power_in"))
      (node (ref "U4") (pin "EXP") (pinfunction "EGND_EXP") (pintype "power_in"))
      (node (ref "U6") (pin "6") (pinfunction "VSS_6") (pintype "power_in"))
      (node (ref "U6") (pin "MT1") (pinfunction "GND_MT1") (pintype "power_in"))
      (node (ref "U6") (pin "MT2") (pinfunction "GND1_MT2") (pintype "power_in"))
    )
    (net (code "49") (name "Net-(CN2-PadD+)") (class "Default")
      (node (ref "CN2") (pin "D+") (pinfunction "D+_D+") (pintype "bidirectional"))
      (node (ref "R21") (pin "2") (pinfunction "2_2") (pintype "passive"))
    )
    (net (code "50") (name "Net-(CN2-PadD-)") (class "Default")
      (node (ref "CN2") (pin "D-") (pinfunction "D-_D-") (pintype "bidirectional"))
      (node (ref "R22") (pin "2") (pinfunction "2_2") (pintype "passive"))
    )
    (net (code "51") (name "Net-(CN2-PadID)") (class "Default")
      (node (ref "CN2") (pin "ID") (pinfunction "ID_ID") (pintype "bidirectional"))
      (node (ref "R23") (pin "2") (pinfunction "2_2") (pintype "passive"))
    )
    (net (code "52") (name "Net-(R15-Pad2)") (class "Default")
      (node (ref "R15") (pin "2") (pinfunction "2_2") (pintype "passive"))
      (node (ref "R19") (pin "2") (pinfunction "2_2") (pintype "passive"))
      (node (ref "X1") (pin "3") (pinfunction "3_3") (pintype "passive"))
    )
    (net (code "53") (name "Net-(SW1A-P)") (class "Default")
      (node (ref "SW1") (pin "2") (pinfunction "P_2") (pintype "passive"))
      (node (ref "U1") (pin "3") (pinfunction "EN_3") (pintype "bidirectional"))
    )
    (net (code "54") (name "Net-(U1-SW)") (class "Default")
      (node (ref "L1") (pin "1") (pinfunction "1_1") (pintype "passive"))
      (node (ref "U1") (pin "5") (pinfunction "SW_5") (pintype "bidirectional"))
    )
    (net (code "55") (name "Net-(U2-PROG1)") (class "Default")
      (node (ref "R6") (pin "2") (pinfunction "2_2") (pintype "passive"))
      (node (ref "U2") (pin "13") (pinfunction "PROG1_13") (pintype "bidirectional"))
    )
    (net (code "56") (name "Net-(U2-PROG3)") (class "Default")
      (node (ref "R7") (pin "2") (pinfunction "2_2") (pintype "passive"))
      (node (ref "U2") (pin "12") (pinfunction "PROG3_12") (pintype "bidirectional"))
    )
    (net (code "57") (name "Net-(U2-THERM)") (class "Default")
      (node (ref "R5") (pin "2") (pinfunction "2_2") (pintype "passive"))
      (node (ref "U2") (pin "5") (pinfunction "THERM_5") (pintype "bidirectional"))
    )
    (net (code "58") (name "Net-(U3-OSC_IN(PH0))") (class "Default")
      (node (ref "C10") (pin "1") (pinfunction "1_1") (pintype "passive"))
      (node (ref "U3") (pin "5") (pinfunction "OSC_IN(PH0)_5") (pintype "bidirectional"))
      (node (ref "Y1") (pin "P$1") (pinfunction "1_P$1") (pintype "passive"))
    )
    (net (code "59") (name "Net-(U3-OSC_OUT(PH1))") (class "Default")
      (node (ref "C11") (pin "1") (pinfunction "1_1") (pintype "passive"))
      (node (ref "U3") (pin "6") (pinfunction "OSC_OUT(PH1)_6") (pintype "bidirectional"))
      (node (ref "Y1") (pin "P$2") (pinfunction "2_P$2") (pintype "passive"))
    )
    (net (code "60") (name "Net-(U3-VCAP_1)") (class "Default")
      (node (ref "C12") (pin "1") (pinfunction "1_1") (pintype "passive"))
      (node (ref "U3") (pin "31") (pinfunction "VCAP_1_31") (pintype "bidirectional"))
    )
    (net (code "61") (name "Net-(U3-VCAP_2)") (class "Default")
      (node (ref "C13") (pin "1") (pinfunction "1_1") (pintype "passive"))
      (node (ref "U3") (pin "47") (pinfunction "VCAP_2_47") (pintype "bidirectional"))
    )
    (net (code "62") (name "Net-(U4-OUTVC12)") (class "Default")
      (node (ref "C16") (pin "+") (pinfunction "+_+") (pintype "passive"))
      (node (ref "C17") (pin "1") (pinfunction "1_1") (pintype "passive"))
      (node (ref "U4") (pin "34") (pinfunction "OUTVC12_34") (pintype "power_in"))
    )
    (net (code "63") (name "Net-(U4-VCM)") (class "Default")
      (node (ref "C14") (pin "1") (pinfunction "1_1") (pintype "passive"))
      (node (ref "C15") (pin "+") (pinfunction "+_+") (pintype "passive"))
      (node (ref "U4") (pin "5") (pinfunction "VCM_5") (pintype "output"))
    )
    (net (code "64") (name "Net-(U5-IN+)") (class "Default")
      (node (ref "R16") (pin "1") (pinfunction "1_1") (pintype "passive"))
      (node (ref "U5") (pin "3") (pinfunction "IN+_3") (pintype "input"))
    )
    (net (code "65") (name "Net-(U5-IN-)") (class "Default")
      (node (ref "R17") (pin "1") (pinfunction "1_1") (pintype "passive"))
      (node (ref "U5") (pin "4") (pinfunction "IN-_4") (pintype "input"))
    )
    (net (code "66") (name "VCC") (class "Default")
      (node (ref "C1") (pin "+") (pinfunction "+_+") (pintype "passive"))
      (node (ref "JP1") (pin "1") (pinfunction "1_1") (pintype "passive"))
      (node (ref "SW1") (pin "1") (pinfunction "S_1") (pintype "passive"))
      (node (ref "U1") (pin "1") (pinfunction "VIN_1") (pintype "bidirectional"))
      (node (ref "U2") (pin "1") (pinfunction "OUT_2_1") (pintype "output"))
      (node (ref "U2") (pin "20") (pinfunction "OUT_20") (pintype "output"))
    )
    (net (code "67") (name "VIN") (class "Default")
      (node (ref "C3") (pin "+") (pinfunction "+_+") (pintype "passive"))
      (node (ref "CN2") (pin "VBUS") (pinfunction "VBUS_VBUS") (pintype "power_in"))
      (node (ref "JP1") (pin "2") (pinfunction "2_2") (pintype "passive"))
      (node (ref "JP4") (pin "2") (pinfunction "2_2") (pintype "passive"))
      (node (ref "R3") (pin "1") (pinfunction "1_1") (pintype "passive"))
      (node (ref "U2") (pin "17") (pinfunction "CE_17") (pintype "input"))
      (node (ref "U2") (pin "18") (pinfunction "IN_2_18") (pintype "input"))
      (node (ref "U2") (pin "19") (pinfunction "IN_19") (pintype "input"))
      (node (ref "U2") (pin "4") (pinfunction "PROG2_4") (pintype "input"))
      (node (ref "U3") (pin "42") (pinfunction "VBUS(PA9)_42") (pintype "bidirectional"))
    )
    (net (code "68") (name "unconnected-(U3-PA1-Pad15)") (class "Default")
      (node (ref "U3") (pin "15") (pinfunction "PA1_15") (pintype "bidirectional"))
    )
    (net (code "69") (name "unconnected-(U3-PA4-Pad20)") (class "Default")
      (node (ref "U3") (pin "20") (pinfunction "PA4_20") (pintype "bidirectional"))
    )
    (net (code "70") (name "unconnected-(U3-PA15-Pad50)") (class "Default")
      (node (ref "U3") (pin "50") (pinfunction "PA15_50") (pintype "bidirectional"))
    )
    (net (code "71") (name "unconnected-(U3-PB8-Pad61)") (class "Default")
      (node (ref "U3") (pin "61") (pinfunction "PB8_61") (pintype "bidirectional"))
    )
    (net (code "72") (name "unconnected-(U3-PB9-Pad62)") (class "Default")
      (node (ref "U3") (pin "62") (pinfunction "PB9_62") (pintype "bidirectional"))
    )
    (net (code "73") (name "unconnected-(U3-PB11-Pad30)") (class "Default")
      (node (ref "U3") (pin "30") (pinfunction "PB11_30") (pintype "bidirectional"))
    )
    (net (code "74") (name "unconnected-(U3-PB14-Pad35)") (class "Default")
      (node (ref "U3") (pin "35") (pinfunction "PB14_35") (pintype "bidirectional"))
    )
    (net (code "75") (name "unconnected-(U3-PB15-Pad36)") (class "Default")
      (node (ref "U3") (pin "36") (pinfunction "PB15_36") (pintype "bidirectional"))
    )
    (net (code "76") (name "unconnected-(U3-PC6-Pad37)") (class "Default")
      (node (ref "U3") (pin "37") (pinfunction "PC6_37") (pintype "bidirectional"))
    )
    (net (code "77") (name "unconnected-(U3-PC7-Pad38)") (class "Default")
      (node (ref "U3") (pin "38") (pinfunction "PC7_38") (pintype "bidirectional"))
    )
    (net (code "78") (name "unconnected-(U3-PC8-Pad39)") (class "Default")
      (node (ref "U3") (pin "39") (pinfunction "PC8_39") (pintype "bidirectional"))
    )
    (net (code "79") (name "unconnected-(U3-PC9-Pad40)") (class "Default")
      (node (ref "U3") (pin "40") (pinfunction "PC9_40") (pintype "bidirectional"))
    )
    (net (code "80") (name "unconnected-(U3-PC12-Pad53)") (class "Default")
      (node (ref "U3") (pin "53") (pinfunction "PC12_53") (pintype "bidirectional"))
    )
    (net (code "81") (name "unconnected-(U3-PC13-Pad2)") (class "Default")
      (node (ref "U3") (pin "2") (pinfunction "PC13_2") (pintype "bidirectional"))
    )
    (net (code "82") (name "unconnected-(U3-PC14-Pad3)") (class "Default")
      (node (ref "U3") (pin "3") (pinfunction "PC14_3") (pintype "bidirectional"))
    )
    (net (code "83") (name "unconnected-(U3-PD2-Pad54)") (class "Default")
      (node (ref "U3") (pin "54") (pinfunction "PD2_54") (pintype "bidirectional"))
    )
    (net (code "84") (name "unconnected-(U4-D0-Pad24)") (class "Default")
      (node (ref "U4") (pin "24") (pinfunction "D0_24") (pintype "bidirectional"))
    )
    (net (code "85") (name "unconnected-(U4-D1-Pad26)") (class "Default")
      (node (ref "U4") (pin "26") (pinfunction "D1_26") (pintype "bidirectional"))
    )
    (net (code "86") (name "unconnected-(U4-D2-Pad27)") (class "Default")
      (node (ref "U4") (pin "27") (pinfunction "D2_27") (pintype "bidirectional"))
    )
    (net (code "87") (name "unconnected-(U4-D3-Pad28)") (class "Default")
      (node (ref "U4") (pin "28") (pinfunction "D3_28") (pintype "bidirectional"))
    )
    (net (code "88") (name "unconnected-(U4-D4-Pad29)") (class "Default")
      (node (ref "U4") (pin "29") (pinfunction "D4_29") (pintype "bidirectional"))
    )
    (net (code "89") (name "unconnected-(U4-D5-Pad30)") (class "Default")
      (node (ref "U4") (pin "30") (pinfunction "D5_30") (pintype "bidirectional"))
    )
    (net (code "90") (name "unconnected-(U4-D6-Pad32)") (class "Default")
      (node (ref "U4") (pin "32") (pinfunction "D6_32") (pintype "bidirectional"))
    )
    (net (code "91") (name "unconnected-(U4-D7-Pad33)") (class "Default")
      (node (ref "U4") (pin "33") (pinfunction "D7_33") (pintype "bidirectional"))
    )
    (net (code "92") (name "unconnected-(U4-MICIN-Pad7)") (class "Default")
      (node (ref "U4") (pin "7") (pinfunction "MICIN_7") (pintype "input"))
    )
    (net (code "93") (name "unconnected-(U4-TEST-Pad37)") (class "Default")
      (node (ref "U4") (pin "37") (pinfunction "TEST_37") (pintype "input"))
    )
    (net (code "94") (name "unconnected-(U4-VCMHPOUT-Pad3)") (class "Default")
      (node (ref "U4") (pin "3") (pinfunction "VCMHPOUT_3") (pintype "output"))
    )
    (net (code "95") (name "unconnected-(U4-X2-Pad40)") (class "Default")
      (node (ref "U4") (pin "40") (pinfunction "X2_40") (pintype "bidirectional"))
    )
    (net (code "96") (name "unconnected-(U5-NC-Pad2)") (class "Default")
      (node (ref "U5") (pin "2") (pinfunction "NC_2") (pintype "no_connect"))
    )
    (net (code "97") (name "unconnected-(U6-CARD_DETECT1-PadCD2)") (class "Default")
      (node (ref "U6") (pin "CD2") (pinfunction "CARD_DETECT1_CD2") (pintype "passive"))
    )
    (net (code "98") (name "unconnected-(U6-DAT1-Pad8)") (class "Default")
      (node (ref "U6") (pin "8") (pinfunction "DAT1_8") (pintype "bidirectional"))
    )
    (net (code "99") (name "unconnected-(U6-DAT2-Pad1)") (class "Default")
      (node (ref "U6") (pin "1") (pinfunction "DAT2_1") (pintype "bidirectional"))
    )
    (net (code "100") (name "unconnected-(X1-Pad4)") (class "Default")
      (node (ref "X1") (pin "4") (pinfunction "4_4") (pintype "passive"))
    )
  )
)
